# blinkm_mk2_3535aa.net
KiCad netlist of a schematic drawn in EAGLE
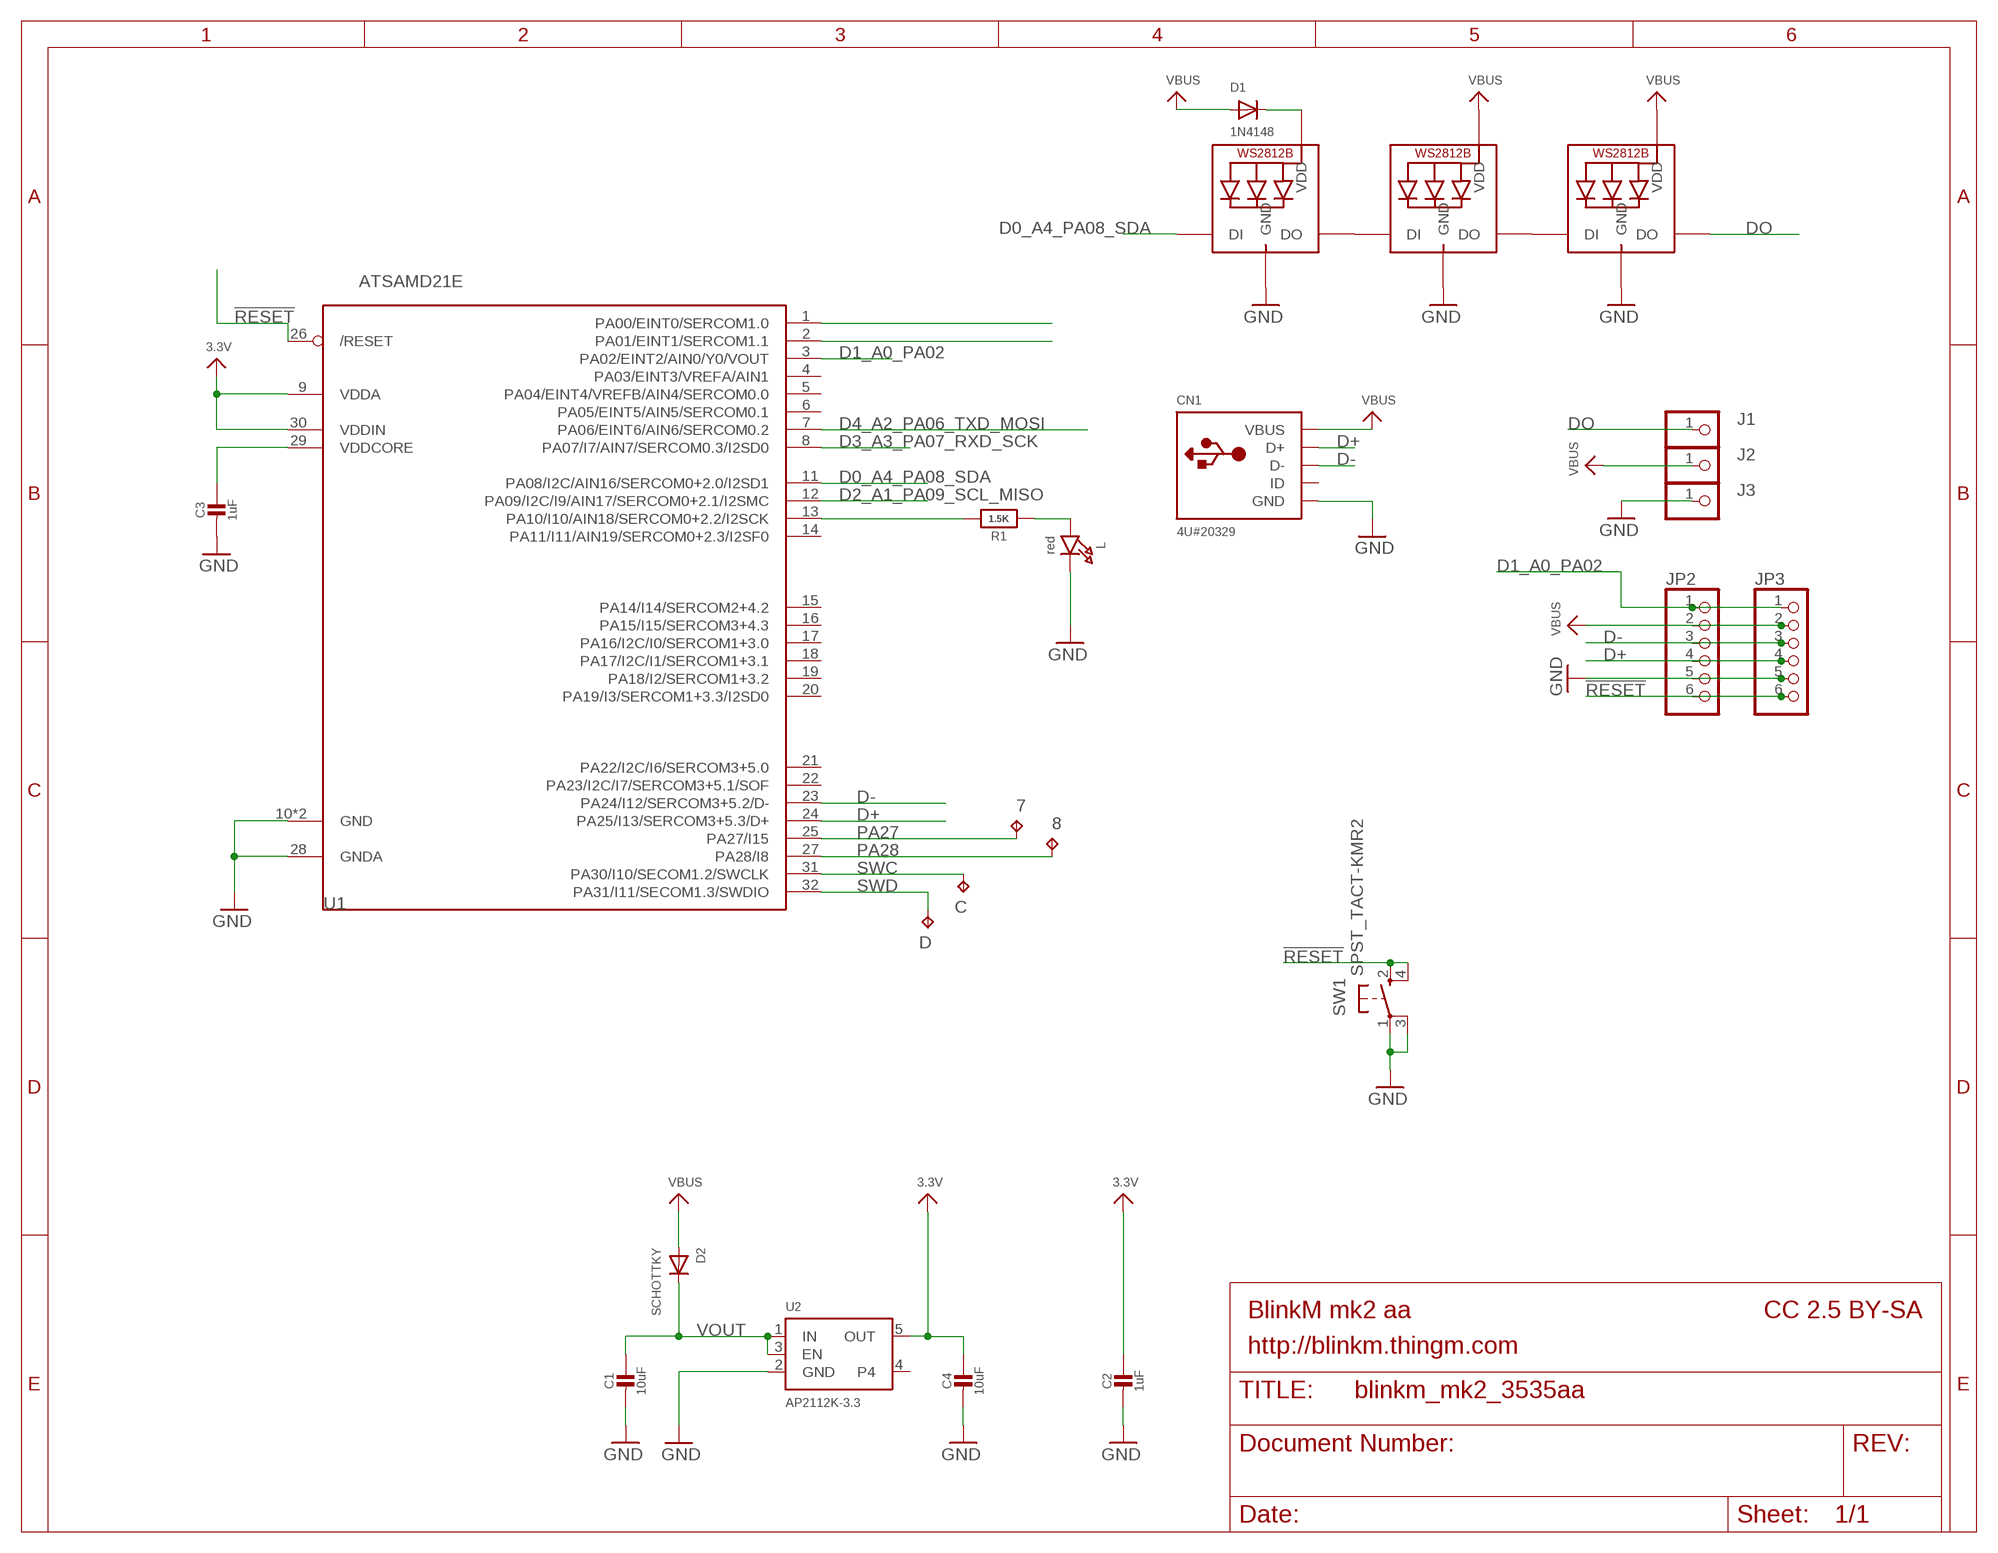
[diagram p0: schematic, sheet 1]

(export (version "E")
  (design (tool "Eeschema 10.0.6"))
  (components
    (comp (ref "7")
      (value "TPTP15R")
      (footprint "eagle-import:TP15R")
      (libsource (lib "eagle-import") (part "TPTP15R"))
    )
    (comp (ref "8")
      (value "TPTP15R")
      (footprint "eagle-import:TP15R")
      (libsource (lib "eagle-import") (part "TPTP15R"))
    )
    (comp (ref "C")
      (value "TPTP15R")
      (footprint "eagle-import:TP15R")
      (libsource (lib "eagle-import") (part "TPTP15R"))
    )
    (comp (ref "C1")
      (value "10uF")
      (footprint "eagle-import:_0402")
      (libsource (lib "eagle-import") (part "CAP_CERAMIC_0402"))
    )
    (comp (ref "C2")
      (value "1uF")
      (footprint "eagle-import:_0402")
      (libsource (lib "eagle-import") (part "CAP_CERAMIC_0402"))
    )
    (comp (ref "C3")
      (value "1uF")
      (footprint "eagle-import:_0402")
      (libsource (lib "eagle-import") (part "CAP_CERAMIC_0402"))
    )
    (comp (ref "C4")
      (value "10uF")
      (footprint "eagle-import:_0402")
      (libsource (lib "eagle-import") (part "CAP_CERAMIC_0402"))
    )
    (comp (ref "CN1")
      (value "4U#20329")
      (footprint "eagle-import:4UCONN_20329_V2")
      (libsource (lib "eagle-import") (part "USB_MICRO_20329_V2"))
    )
    (comp (ref "D")
      (value "TPTP15R")
      (footprint "eagle-import:TP15R")
      (libsource (lib "eagle-import") (part "TPTP15R"))
    )
    (comp (ref "D1")
      (value "1N4148")
      (footprint "eagle-import:SOD-523")
      (libsource (lib "eagle-import") (part "adafruit_420_DIODESOD-523"))
    )
    (comp (ref "D2")
      (value "SCHOTTKY")
      (footprint "eagle-import:SOD-523")
      (libsource (lib "eagle-import") (part "DIODESOD-523"))
    )
    (comp (ref "J1")
      (value "PINHD-1X1")
      (footprint "eagle-import:1X01")
      (libsource (lib "eagle-import") (part "PINHD-1X1"))
    )
    (comp (ref "J2")
      (value "PINHD-1X1")
      (footprint "eagle-import:1X01")
      (libsource (lib "eagle-import") (part "PINHD-1X1"))
    )
    (comp (ref "J3")
      (value "PINHD-1X1")
      (footprint "eagle-import:1X01")
      (libsource (lib "eagle-import") (part "PINHD-1X1"))
    )
    (comp (ref "JP2")
      (value "PINHD-1X6")
      (footprint "eagle-import:1X06")
      (libsource (lib "eagle-import") (part "PINHD-1X6"))
    )
    (comp (ref "JP3")
      (value "PINHD-1X6")
      (footprint "eagle-import:1X06")
      (libsource (lib "eagle-import") (part "PINHD-1X6"))
    )
    (comp (ref "L")
      (value "red")
      (footprint "eagle-import:CHIPLED_0603_NOOUTLINE")
      (libsource (lib "eagle-import") (part "LED0603_NOOUTLINE"))
    )
    (comp (ref "L1")
      (value "WS2812B3535")
      (footprint "eagle-import:LED3535")
      (libsource (lib "eagle-import") (part "WS2812B3535"))
    )
    (comp (ref "L2")
      (value "WS2812B3535")
      (footprint "eagle-import:LED3535")
      (libsource (lib "eagle-import") (part "WS2812B3535"))
    )
    (comp (ref "L3")
      (value "WS2812B3535")
      (footprint "eagle-import:LED3535")
      (libsource (lib "eagle-import") (part "WS2812B3535"))
    )
    (comp (ref "R1")
      (value "1.5K")
      (footprint "eagle-import:_0402")
      (libsource (lib "eagle-import") (part "RESISTOR_0402"))
    )
    (comp (ref "SW1")
      (value "SPST_TACT-KMR2")
      (footprint "eagle-import:KMR2")
      (libsource (lib "eagle-import") (part "SPST_TACT-KMR2"))
    )
    (comp (ref "U1")
      (value "ATSAMD21E")
      (footprint "eagle-import:QFN32_5MM")
      (libsource (lib "eagle-import") (part "ATSAMD21E"))
    )
    (comp (ref "U2")
      (value "AP2112K-3.3")
      (footprint "eagle-import:SOT23-5")
      (libsource (lib "eagle-import") (part "VREG_SOT23-5"))
    )
  )
  (nets
    (net (code "1") (name "/D+") (class "Default")
      (node (ref "CN1") (pin "D+") (pinfunction "D+_D+") (pintype "bidirectional"))
      (node (ref "JP2") (pin "4") (pinfunction "4_4") (pintype "passive"))
      (node (ref "JP3") (pin "4") (pinfunction "4_4") (pintype "passive"))
      (node (ref "U1") (pin "24") (pinfunction "PA25/I13/SERCOM3+5.3/D+_24") (pintype "bidirectional"))
    )
    (net (code "2") (name "/D-") (class "Default")
      (node (ref "CN1") (pin "D-") (pinfunction "D-_D-") (pintype "bidirectional"))
      (node (ref "JP2") (pin "3") (pinfunction "3_3") (pintype "passive"))
      (node (ref "JP3") (pin "3") (pinfunction "3_3") (pintype "passive"))
      (node (ref "U1") (pin "23") (pinfunction "PA24/I12/SERCOM3+5.2/D-_23") (pintype "bidirectional"))
    )
    (net (code "3") (name "/D0_A4_PA08_SDA") (class "Default")
      (node (ref "L1") (pin "1") (pinfunction "DI_1") (pintype "input"))
      (node (ref "U1") (pin "11") (pinfunction "PA08/I2C/AIN16/SERCOM0+2.0/I2SD1_11") (pintype "bidirectional"))
    )
    (net (code "4") (name "/D1_A0_PA02") (class "Default")
      (node (ref "JP2") (pin "1") (pinfunction "1_1") (pintype "passive"))
      (node (ref "JP3") (pin "1") (pinfunction "1_1") (pintype "passive"))
      (node (ref "U1") (pin "3") (pinfunction "PA02/EINT2/AIN0/Y0/VOUT_3") (pintype "bidirectional"))
    )
    (net (code "5") (name "/D2_A1_PA09_SCL_MISO") (class "Default")
      (node (ref "U1") (pin "12") (pinfunction "PA09/I2C/I9/AIN17/SERCOM0+2.1/I2SMC_12") (pintype "bidirectional"))
    )
    (net (code "6") (name "/D3_A3_PA07_RXD_SCK") (class "Default")
      (node (ref "U1") (pin "8") (pinfunction "PA07/I7/AIN7/SERCOM0.3/I2SD0_8") (pintype "bidirectional"))
    )
    (net (code "7") (name "/D4_A2_PA06_TXD_MOSI") (class "Default")
      (node (ref "U1") (pin "7") (pinfunction "PA06/EINT6/AIN6/SERCOM0.2_7") (pintype "bidirectional"))
    )
    (net (code "8") (name "/DO") (class "Default")
      (node (ref "J1") (pin "1") (pinfunction "1_1") (pintype "passive"))
      (node (ref "L3") (pin "3") (pinfunction "DO_3") (pintype "output"))
    )
    (net (code "9") (name "/PA27") (class "Default")
      (node (ref "7") (pin "TP") (pinfunction "TP_TP") (pintype "input"))
      (node (ref "U1") (pin "25") (pinfunction "PA27/I15_25") (pintype "bidirectional"))
    )
    (net (code "10") (name "/PA28") (class "Default")
      (node (ref "8") (pin "TP") (pinfunction "TP_TP") (pintype "input"))
      (node (ref "U1") (pin "27") (pinfunction "PA28/I8_27") (pintype "bidirectional"))
    )
    (net (code "11") (name "/SWC") (class "Default")
      (node (ref "C") (pin "TP") (pinfunction "TP_TP") (pintype "input"))
      (node (ref "U1") (pin "31") (pinfunction "PA30/I10/SECOM1.2/SWCLK_31") (pintype "bidirectional"))
    )
    (net (code "12") (name "/SWD") (class "Default")
      (node (ref "D") (pin "TP") (pinfunction "TP_TP") (pintype "input"))
      (node (ref "U1") (pin "32") (pinfunction "PA31/I11/SECOM1.3/SWDIO_32") (pintype "bidirectional"))
    )
    (net (code "13") (name "/VOUT") (class "Default")
      (node (ref "C1") (pin "1") (pinfunction "1_1") (pintype "passive"))
      (node (ref "D2") (pin "K") (pinfunction "C_K") (pintype "passive"))
      (node (ref "U2") (pin "1") (pinfunction "IN_1") (pintype "power_in"))
      (node (ref "U2") (pin "3") (pinfunction "EN_3") (pintype "input"))
    )
    (net (code "14") (name "/~{RESET}") (class "Default")
      (node (ref "JP2") (pin "6") (pinfunction "6_6") (pintype "passive"))
      (node (ref "JP3") (pin "6") (pinfunction "6_6") (pintype "passive"))
      (node (ref "SW1") (pin "2") (pinfunction "S_2") (pintype "passive"))
      (node (ref "SW1") (pin "4") (pinfunction "S1_4") (pintype "passive"))
      (node (ref "U1") (pin "26") (pinfunction "/RESET_26") (pintype "bidirectional"))
    )
    (net (code "15") (name "3.3V") (class "Default")
      (node (ref "C2") (pin "1") (pinfunction "1_1") (pintype "passive"))
      (node (ref "C4") (pin "1") (pinfunction "1_1") (pintype "passive"))
      (node (ref "U1") (pin "30") (pinfunction "VDDIN_30") (pintype "power_in"))
      (node (ref "U1") (pin "9") (pinfunction "VDDA_9") (pintype "power_in"))
      (node (ref "U2") (pin "5") (pinfunction "OUT_5") (pintype "power_in"))
    )
    (net (code "16") (name "GND") (class "Default")
      (node (ref "C1") (pin "2") (pinfunction "2_2") (pintype "passive"))
      (node (ref "C2") (pin "2") (pinfunction "2_2") (pintype "passive"))
      (node (ref "C3") (pin "2") (pinfunction "2_2") (pintype "passive"))
      (node (ref "C4") (pin "2") (pinfunction "2_2") (pintype "passive"))
      (node (ref "CN1") (pin "BASE@1") (pinfunction "GND_BASE@1") (pintype "power_in"))
      (node (ref "CN1") (pin "BASE@2") (pinfunction "GND_BASE@2") (pintype "power_in"))
      (node (ref "CN1") (pin "GND") (pinfunction "GND_GND") (pintype "power_in"))
      (node (ref "CN1") (pin "SPRT@1") (pinfunction "GND_SPRT@1") (pintype "power_in"))
      (node (ref "CN1") (pin "SPRT@2") (pinfunction "GND_SPRT@2") (pintype "power_in"))
      (node (ref "CN1") (pin "SPRT@3") (pinfunction "GND_SPRT@3") (pintype "power_in"))
      (node (ref "CN1") (pin "SPRT@4") (pinfunction "GND_SPRT@4") (pintype "power_in"))
      (node (ref "J3") (pin "1") (pinfunction "1_1") (pintype "passive"))
      (node (ref "JP2") (pin "5") (pinfunction "5_5") (pintype "passive"))
      (node (ref "JP3") (pin "5") (pinfunction "5_5") (pintype "passive"))
      (node (ref "L") (pin "C") (pinfunction "C_C") (pintype "passive"))
      (node (ref "L1") (pin "4") (pinfunction "GND_4") (pintype "power_in"))
      (node (ref "L2") (pin "4") (pinfunction "GND_4") (pintype "power_in"))
      (node (ref "L3") (pin "4") (pinfunction "GND_4") (pintype "power_in"))
      (node (ref "SW1") (pin "1") (pinfunction "P_1") (pintype "passive"))
      (node (ref "SW1") (pin "3") (pinfunction "P1_3") (pintype "passive"))
      (node (ref "U1") (pin "10") (pinfunction "GND_10") (pintype "power_in"))
      (node (ref "U1") (pin "28") (pinfunction "GNDA_28") (pintype "power_in"))
      (node (ref "U1") (pin "33") (pinfunction "GND_33") (pintype "power_in"))
      (node (ref "U2") (pin "2") (pinfunction "GND_2") (pintype "power_in"))
    )
    (net (code "17") (name "Net-(D1-C)") (class "Default")
      (node (ref "D1") (pin "K") (pinfunction "C_K") (pintype "passive"))
      (node (ref "L1") (pin "2") (pinfunction "VDD_2") (pintype "power_in"))
    )
    (net (code "18") (name "Net-(L-PadA)") (class "Default")
      (node (ref "L") (pin "A") (pinfunction "A_A") (pintype "passive"))
      (node (ref "R1") (pin "1") (pinfunction "1_1") (pintype "passive"))
    )
    (net (code "19") (name "Net-(L1-DO)") (class "Default")
      (node (ref "L1") (pin "3") (pinfunction "DO_3") (pintype "output"))
      (node (ref "L2") (pin "1") (pinfunction "DI_1") (pintype "input"))
    )
    (net (code "20") (name "Net-(L2-DO)") (class "Default")
      (node (ref "L2") (pin "3") (pinfunction "DO_3") (pintype "output"))
      (node (ref "L3") (pin "1") (pinfunction "DI_1") (pintype "input"))
    )
    (net (code "21") (name "Net-(U1-PA10{slash}I10{slash}AIN18{slash}SERCOM0+2.2{slash}I2SCK)") (class "Default")
      (node (ref "R1") (pin "2") (pinfunction "2_2") (pintype "passive"))
      (node (ref "U1") (pin "13") (pinfunction "PA10/I10/AIN18/SERCOM0+2.2/I2SCK_13") (pintype "bidirectional"))
    )
    (net (code "22") (name "Net-(U1-VDDCORE)") (class "Default")
      (node (ref "C3") (pin "1") (pinfunction "1_1") (pintype "passive"))
      (node (ref "U1") (pin "29") (pinfunction "VDDCORE_29") (pintype "power_in"))
    )
    (net (code "23") (name "VBUS") (class "Default")
      (node (ref "CN1") (pin "VBUS") (pinfunction "VBUS_VBUS") (pintype "power_in"))
      (node (ref "D1") (pin "A") (pinfunction "A_A") (pintype "passive"))
      (node (ref "D2") (pin "A") (pinfunction "A_A") (pintype "passive"))
      (node (ref "J2") (pin "1") (pinfunction "1_1") (pintype "passive"))
      (node (ref "JP2") (pin "2") (pinfunction "2_2") (pintype "passive"))
      (node (ref "JP3") (pin "2") (pinfunction "2_2") (pintype "passive"))
      (node (ref "L2") (pin "2") (pinfunction "VDD_2") (pintype "power_in"))
      (node (ref "L3") (pin "2") (pinfunction "VDD_2") (pintype "power_in"))
    )
    (net (code "24") (name "unconnected-(CN1-PadID)") (class "Default")
      (node (ref "CN1") (pin "ID") (pinfunction "ID_ID") (pintype "bidirectional"))
    )
    (net (code "25") (name "unconnected-(U1-PA00{slash}EINT0{slash}SERCOM1.0-Pad1)") (class "Default")
      (node (ref "U1") (pin "1") (pinfunction "PA00/EINT0/SERCOM1.0_1") (pintype "bidirectional"))
    )
    (net (code "26") (name "unconnected-(U1-PA01{slash}EINT1{slash}SERCOM1.1-Pad2)") (class "Default")
      (node (ref "U1") (pin "2") (pinfunction "PA01/EINT1/SERCOM1.1_2") (pintype "bidirectional"))
    )
    (net (code "27") (name "unconnected-(U1-PA03{slash}EINT3{slash}VREFA{slash}AIN1-Pad4)") (class "Default")
      (node (ref "U1") (pin "4") (pinfunction "PA03/EINT3/VREFA/AIN1_4") (pintype "bidirectional"))
    )
    (net (code "28") (name "unconnected-(U1-PA04{slash}EINT4{slash}VREFB{slash}AIN4{slash}SERCOM0.0-Pad5)") (class "Default")
      (node (ref "U1") (pin "5") (pinfunction "PA04/EINT4/VREFB/AIN4/SERCOM0.0_5") (pintype "bidirectional"))
    )
    (net (code "29") (name "unconnected-(U1-PA05{slash}EINT5{slash}AIN5{slash}SERCOM0.1-Pad6)") (class "Default")
      (node (ref "U1") (pin "6") (pinfunction "PA05/EINT5/AIN5/SERCOM0.1_6") (pintype "bidirectional"))
    )
    (net (code "30") (name "unconnected-(U1-PA11{slash}I11{slash}AIN19{slash}SERCOM0+2.3{slash}I2SF0-Pad14)") (class "Default")
      (node (ref "U1") (pin "14") (pinfunction "PA11/I11/AIN19/SERCOM0+2.3/I2SF0_14") (pintype "bidirectional"))
    )
    (net (code "31") (name "unconnected-(U1-PA14{slash}I14{slash}SERCOM2+4.2-Pad15)") (class "Default")
      (node (ref "U1") (pin "15") (pinfunction "PA14/I14/SERCOM2+4.2_15") (pintype "bidirectional"))
    )
    (net (code "32") (name "unconnected-(U1-PA15{slash}I15{slash}SERCOM3+4.3-Pad16)") (class "Default")
      (node (ref "U1") (pin "16") (pinfunction "PA15/I15/SERCOM3+4.3_16") (pintype "bidirectional"))
    )
    (net (code "33") (name "unconnected-(U1-PA16{slash}I2C{slash}I0{slash}SERCOM1+3.0-Pad17)") (class "Default")
      (node (ref "U1") (pin "17") (pinfunction "PA16/I2C/I0/SERCOM1+3.0_17") (pintype "bidirectional"))
    )
    (net (code "34") (name "unconnected-(U1-PA17{slash}I2C{slash}I1{slash}SERCOM1+3.1-Pad18)") (class "Default")
      (node (ref "U1") (pin "18") (pinfunction "PA17/I2C/I1/SERCOM1+3.1_18") (pintype "bidirectional"))
    )
    (net (code "35") (name "unconnected-(U1-PA18{slash}I2{slash}SERCOM1+3.2-Pad19)") (class "Default")
      (node (ref "U1") (pin "19") (pinfunction "PA18/I2/SERCOM1+3.2_19") (pintype "bidirectional"))
    )
    (net (code "36") (name "unconnected-(U1-PA19{slash}I3{slash}SERCOM1+3.3{slash}I2SD0-Pad20)") (class "Default")
      (node (ref "U1") (pin "20") (pinfunction "PA19/I3/SERCOM1+3.3/I2SD0_20") (pintype "bidirectional"))
    )
    (net (code "37") (name "unconnected-(U1-PA22{slash}I2C{slash}I6{slash}SERCOM3+5.0-Pad21)") (class "Default")
      (node (ref "U1") (pin "21") (pinfunction "PA22/I2C/I6/SERCOM3+5.0_21") (pintype "bidirectional"))
    )
    (net (code "38") (name "unconnected-(U1-PA23{slash}I2C{slash}I7{slash}SERCOM3+5.1{slash}SOF-Pad22)") (class "Default")
      (node (ref "U1") (pin "22") (pinfunction "PA23/I2C/I7/SERCOM3+5.1/SOF_22") (pintype "bidirectional"))
    )
    (net (code "39") (name "unconnected-(U2-P4-Pad4)") (class "Default")
      (node (ref "U2") (pin "4") (pinfunction "P4_4") (pintype "bidirectional"))
    )
  )
)
